# PCA_0005_FULL_CB_tp_REV_B.net
KiCad netlist of a schematic drawn in Altium Designer
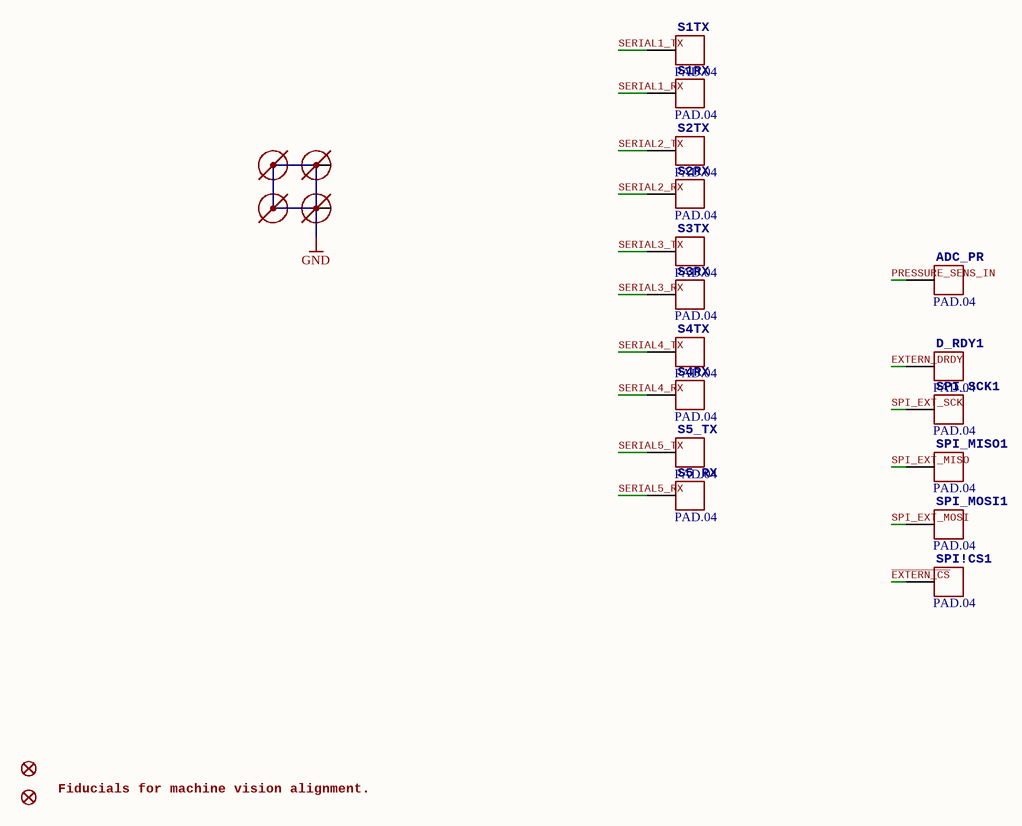
[diagram p0: PCA_0005_FULL_CB_tp_REV_B.SchDoc]

(export (version "E")
  (design (tool "Eeschema 10.0.6"))
  (components
    (comp (ref "ADC_PR")
      (value "PAD.04")
      (footprint "PAD.04X.04")
      (libsource (lib "pixhawk2") (part "PAD.04"))
    )
    (comp (ref "D_RDY1")
      (value "PAD.04")
      (footprint "PAD.04X.04")
      (libsource (lib "pixhawk2") (part "PAD.04"))
    )
    (comp (ref "JP400")
      (value "FIDUCIAL1.5X3")
      (footprint "FIDUCIAL-1.5X3")
      (description "<b>Fiducial Alignment Points</b>\nVarious fiducial points for machine vision alignment.")
      (libsource (lib "pixhawk2") (part "FIDUCIAL1.5X3"))
    )
    (comp (ref "JP401")
      (value "FIDUCIAL1.5X3")
      (footprint "FIDUCIAL-1.5X3")
      (description "<b>Fiducial Alignment Points</b>\nVarious fiducial points for machine vision alignment.")
      (libsource (lib "pixhawk2") (part "FIDUCIAL1.5X3"))
    )
    (comp (ref "M3_MOUNT901")
      (value "MOUNT-HOLE1.8MM")
      (footprint "MOUNT-HOLE1.8")
      (libsource (lib "pixhawk2") (part "MOUNT-HOLE1.8MM"))
    )
    (comp (ref "M3_MOUNT902")
      (value "MOUNT-HOLE1.8MM")
      (footprint "MOUNT-HOLE1.8")
      (libsource (lib "pixhawk2") (part "MOUNT-HOLE1.8MM"))
    )
    (comp (ref "M3_MOUNT903")
      (value "MOUNT-HOLE1.8MM")
      (footprint "MOUNT-HOLE1.8")
      (libsource (lib "pixhawk2") (part "MOUNT-HOLE1.8MM"))
    )
    (comp (ref "M3_MOUNT904")
      (value "MOUNT-HOLE1.8MM")
      (footprint "MOUNT-HOLE1.8")
      (libsource (lib "pixhawk2") (part "MOUNT-HOLE1.8MM"))
    )
    (comp (ref "S1RX") (value "PAD.04") (footprint "PAD.04X.04") (libsource (lib "pixhawk2") (part "PAD.04")))
    (comp (ref "S1TX") (value "PAD.04") (footprint "PAD.04X.04") (libsource (lib "pixhawk2") (part "PAD.04")))
    (comp (ref "S2RX") (value "PAD.04") (footprint "PAD.04X.04") (libsource (lib "pixhawk2") (part "PAD.04")))
    (comp (ref "S2TX") (value "PAD.04") (footprint "PAD.04X.04") (libsource (lib "pixhawk2") (part "PAD.04")))
    (comp (ref "S3RX") (value "PAD.04") (footprint "PAD.04X.04") (libsource (lib "pixhawk2") (part "PAD.04")))
    (comp (ref "S3TX") (value "PAD.04") (footprint "PAD.04X.04") (libsource (lib "pixhawk2") (part "PAD.04")))
    (comp (ref "S4RX") (value "PAD.04") (footprint "PAD.04X.04") (libsource (lib "pixhawk2") (part "PAD.04")))
    (comp (ref "S4TX") (value "PAD.04") (footprint "PAD.04X.04") (libsource (lib "pixhawk2") (part "PAD.04")))
    (comp (ref "S5_RX")
      (value "PAD.04")
      (footprint "PAD.04X.04")
      (libsource (lib "pixhawk2") (part "PAD.04"))
    )
    (comp (ref "S5_TX")
      (value "PAD.04")
      (footprint "PAD.04X.04")
      (libsource (lib "pixhawk2") (part "PAD.04"))
    )
    (comp (ref "SPI!CS1")
      (value "PAD.04")
      (footprint "PAD.04X.04")
      (libsource (lib "pixhawk2") (part "PAD.04"))
    )
    (comp (ref "SPI_MISO1")
      (value "PAD.04")
      (footprint "PAD.04X.04")
      (libsource (lib "pixhawk2") (part "PAD.04"))
    )
    (comp (ref "SPI_MOSI1")
      (value "PAD.04")
      (footprint "PAD.04X.04")
      (libsource (lib "pixhawk2") (part "PAD.04"))
    )
    (comp (ref "SPI_SCK1")
      (value "PAD.04")
      (footprint "PAD.04X.04")
      (libsource (lib "pixhawk2") (part "PAD.04"))
    )
  )
  (nets
    (net (code "1") (name "/EXTERN_DRDY") (class "Default")
      (node (ref "D_RDY1") (pin "P$1") (pinfunction "P$1_P$1") (pintype "passive"))
    )
    (net (code "2") (name "/PRESSURE_SENS_IN") (class "Default")
      (node (ref "ADC_PR") (pin "P$1") (pinfunction "P$1_P$1") (pintype "passive"))
    )
    (net (code "3") (name "/SERIAL1_RX") (class "Default")
      (node (ref "S1RX") (pin "P$1") (pinfunction "P$1_P$1") (pintype "passive"))
    )
    (net (code "4") (name "/SERIAL1_TX") (class "Default")
      (node (ref "S1TX") (pin "P$1") (pinfunction "P$1_P$1") (pintype "passive"))
    )
    (net (code "5") (name "/SERIAL2_RX") (class "Default")
      (node (ref "S2RX") (pin "P$1") (pinfunction "P$1_P$1") (pintype "passive"))
    )
    (net (code "6") (name "/SERIAL2_TX") (class "Default")
      (node (ref "S2TX") (pin "P$1") (pinfunction "P$1_P$1") (pintype "passive"))
    )
    (net (code "7") (name "/SERIAL3_RX") (class "Default")
      (node (ref "S3RX") (pin "P$1") (pinfunction "P$1_P$1") (pintype "passive"))
    )
    (net (code "8") (name "/SERIAL3_TX") (class "Default")
      (node (ref "S3TX") (pin "P$1") (pinfunction "P$1_P$1") (pintype "passive"))
    )
    (net (code "9") (name "/SERIAL4_RX") (class "Default")
      (node (ref "S4RX") (pin "P$1") (pinfunction "P$1_P$1") (pintype "passive"))
    )
    (net (code "10") (name "/SERIAL4_TX") (class "Default")
      (node (ref "S4TX") (pin "P$1") (pinfunction "P$1_P$1") (pintype "passive"))
    )
    (net (code "11") (name "/SERIAL5_RX") (class "Default")
      (node (ref "S5_RX") (pin "P$1") (pinfunction "P$1_P$1") (pintype "passive"))
    )
    (net (code "12") (name "/SERIAL5_TX") (class "Default")
      (node (ref "S5_TX") (pin "P$1") (pinfunction "P$1_P$1") (pintype "passive"))
    )
    (net (code "13") (name "/SPI_EXT_MISO") (class "Default")
      (node (ref "SPI_MISO1") (pin "P$1") (pinfunction "P$1_P$1") (pintype "passive"))
    )
    (net (code "14") (name "/SPI_EXT_MOSI") (class "Default")
      (node (ref "SPI_MOSI1") (pin "P$1") (pinfunction "P$1_P$1") (pintype "passive"))
    )
    (net (code "15") (name "/SPI_EXT_SCK") (class "Default")
      (node (ref "SPI_SCK1") (pin "P$1") (pinfunction "P$1_P$1") (pintype "passive"))
    )
    (net (code "16") (name "/~{EXTERN_CS}") (class "Default")
      (node (ref "SPI!CS1") (pin "P$1") (pinfunction "P$1_P$1") (pintype "passive"))
    )
    (net (code "17") (name "GND") (class "Default")
      (node (ref "M3_MOUNT901") (pin "1") (pinfunction "1_1") (pintype "passive"))
      (node (ref "M3_MOUNT902") (pin "1") (pinfunction "1_1") (pintype "passive"))
      (node (ref "M3_MOUNT903") (pin "1") (pinfunction "1_1") (pintype "passive"))
      (node (ref "M3_MOUNT904") (pin "1") (pinfunction "1_1") (pintype "passive"))
    )
  )
)
